# PX4FMUv2_4_6_08.net
KiCad netlist of a schematic drawn in Altium Designer
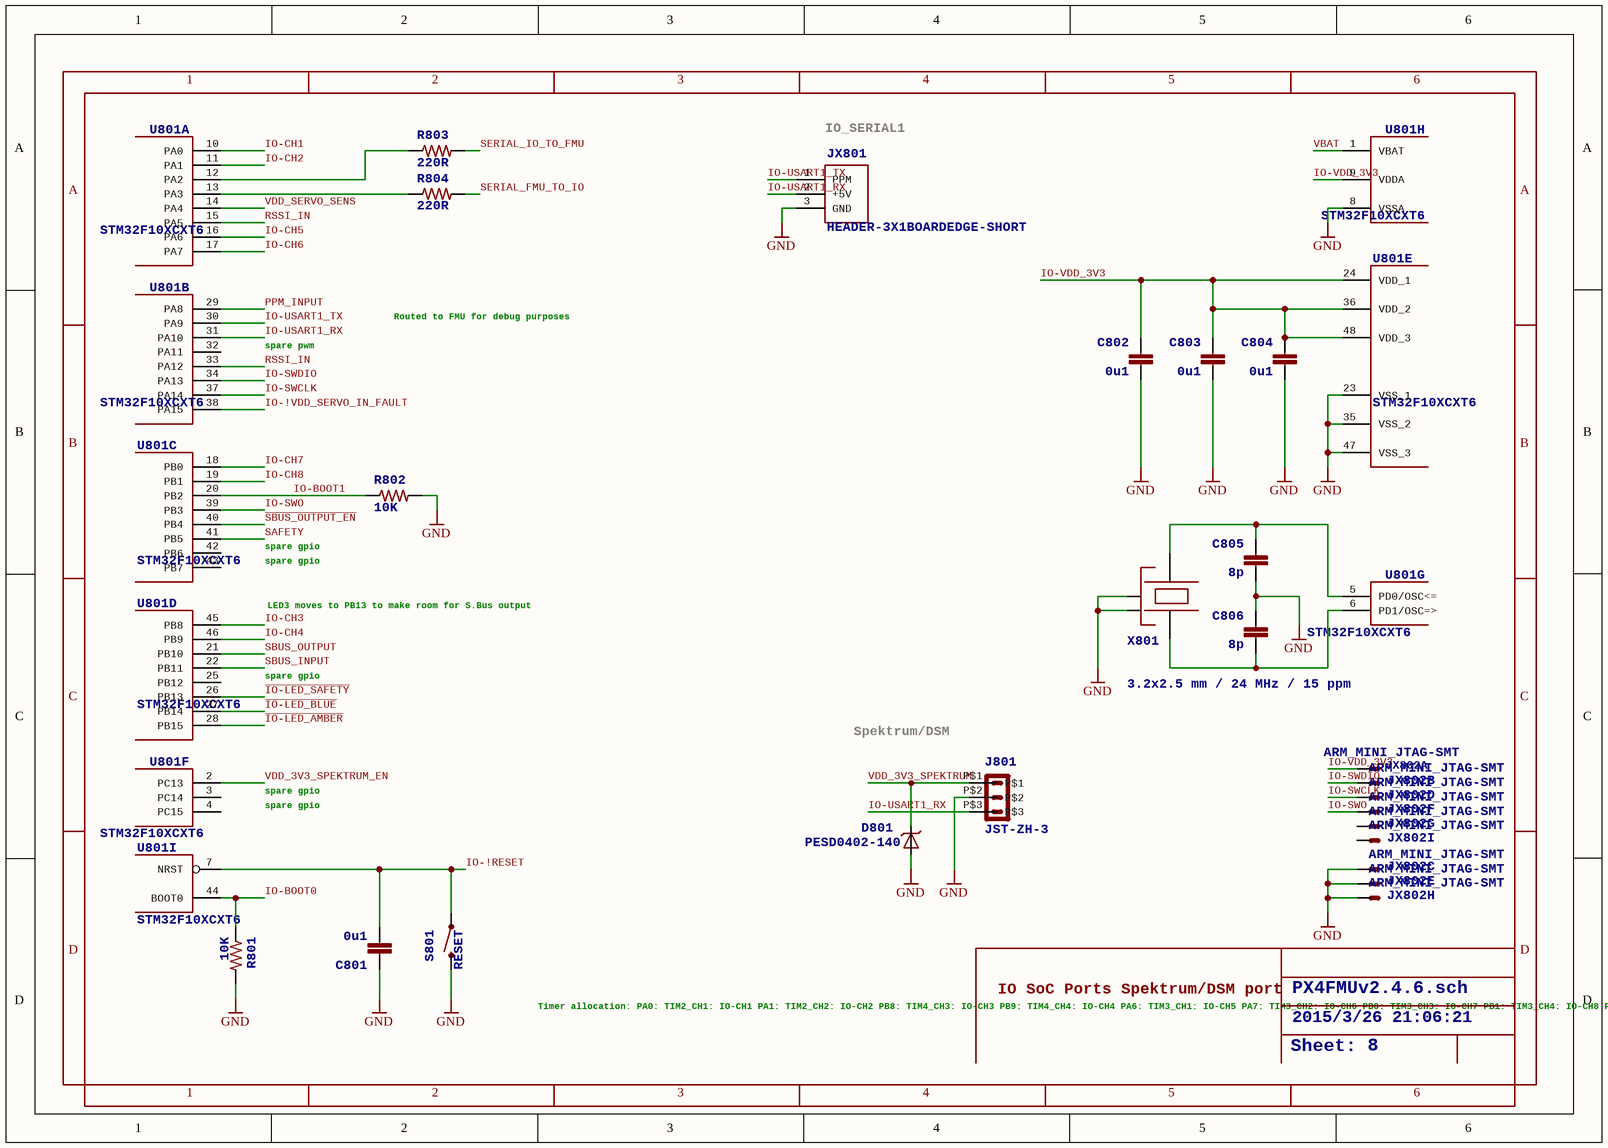
[diagram p0: PX4FMUv2.4.6_08.SchDoc]

(export (version "E")
  (design (tool "Eeschema 10.0.6"))
  (components
    (comp (ref "C801")
      (value "0u1")
      (footprint "0402-CAP")
      (description "<b>Capacitor</b>\nStandard 0603 ceramic capacitor, and 0.1\" leaded capacitor.")
      (fields (field (name "PARTNO") "CC0402ZRY5V7BB104"))
      (libsource (lib "") (part "CAP0402_1"))
    )
    (comp (ref "C802")
      (value "0u1")
      (footprint "0402-CAP")
      (description "<b>Capacitor</b>\nStandard 0603 ceramic capacitor, and 0.1\" leaded capacitor.")
      (fields (field (name "PARTNO") "CC0402ZRY5V7BB104"))
      (libsource (lib "pixhawk2") (part "CAP0402"))
    )
    (comp (ref "C803")
      (value "0u1")
      (footprint "0402-CAP")
      (description "<b>Capacitor</b>\nStandard 0603 ceramic capacitor, and 0.1\" leaded capacitor.")
      (fields (field (name "PARTNO") "CC0402ZRY5V7BB104"))
      (libsource (lib "pixhawk2") (part "CAP0402"))
    )
    (comp (ref "C804")
      (value "0u1")
      (footprint "0402-CAP")
      (description "<b>Capacitor</b>\nStandard 0603 ceramic capacitor, and 0.1\" leaded capacitor.")
      (fields (field (name "PARTNO") "CC0402ZRY5V7BB104"))
      (libsource (lib "pixhawk2") (part "CAP0402"))
    )
    (comp (ref "C805")
      (value "8p")
      (footprint "0402-CAP")
      (description "<b>Capacitor</b>\nStandard 0603 ceramic capacitor, and 0.1\" leaded capacitor.")
      (fields (field (name "PARTNO") "C1005C0G1H080C"))
      (libsource (lib "pixhawk2") (part "CAP0402"))
    )
    (comp (ref "C806")
      (value "8p")
      (footprint "0402-CAP")
      (description "<b>Capacitor</b>\nStandard 0603 ceramic capacitor, and 0.1\" leaded capacitor.")
      (fields (field (name "PARTNO") "C1005C0G1H080C"))
      (libsource (lib "pixhawk2") (part "CAP0402"))
    )
    (comp (ref "D801")
      (value "PESD0402-140")
      (footprint "0402-TVS")
      (libsource (lib "pixhawk2") (part "DIODE-TVS"))
    )
    (comp (ref "J801")
      (value "JST-ZH-3")
      (footprint "JST-ZH-SMT-VERTICAL")
      (fields (field (name "PARTNO") "B3B-ZR-SM4-TF (LF)(SN)(P)"))
      (libsource (lib "for-transfers") (part "JST-ZH-3"))
    )
    (comp (ref "JX801")
      (value "HEADER-3X1BOARDEDGE-SHORT")
      (footprint "HEADER_3X01_SMD_H_BOARD_EDGE_SHORT")
      (description "<h3>Single row 0.1\" servo header</h3>")
      (libsource (lib "pixhawk2") (part "HEADER-3X1BOARDEDGE-SHORT"))
    )
    (comp (ref "JX802")
      (value "ARM_MINI_JTAG-SMT")
      (footprint "FTSH-105-01-XXX-DV-K")
      (description "<b>CONNECTOR</b><p>\nwire to board 1.25 mm (.049 inch) pitch header")
      (fields (field (name "PARTNO") "M50-3900542"))
      (libsource (lib "pixhawk2") (part "ARM_MINI_JTAG-SMT"))
    )
    (comp (ref "R801")
      (value "10K")
      (footprint "0402-RES")
      (fields (field (name "PARTNO") "RC0402FR-0710KL"))
      (libsource (lib "pixhawk2") (part "RESISTOR0402-RES"))
    )
    (comp (ref "R802")
      (value "10K")
      (footprint "0402-RES")
      (fields (field (name "PARTNO") "RC0402FR-0710KL"))
      (libsource (lib "pixhawk2") (part "RESISTOR0402-RES"))
    )
    (comp (ref "R803")
      (value "220R")
      (footprint "0402-RES")
      (fields (field (name "PARTNO") "RC0402FR-07220RL"))
      (libsource (lib "pixhawk2") (part "RESISTOR0402-RES"))
    )
    (comp (ref "R804")
      (value "220R")
      (footprint "0402-RES")
      (fields (field (name "PARTNO") "RC0402FR-07220RL"))
      (libsource (lib "pixhawk2") (part "RESISTOR0402-RES"))
    )
    (comp (ref "S801")
      (value "RESET")
      (footprint "EVQP7J01K")
      (fields (field (name "PARTNO") "EVQ-P7J01P"))
      (libsource (lib "pixhawk2") (part "SWITCH-MOMENTARY-2"))
    )
    (comp (ref "U801")
      (value "STM32F10XCXT6")
      (footprint "TQFP48")
      (description "ST STM32F101/103 48pin LQFP")
      (fields (field (name "PARTNO") "STM32F100C8T6B"))
      (libsource (lib "pixhawk2") (part "STM32F10XCXT6"))
    )
    (comp (ref "X801")
      (value "3.2x2.5 mm / 24 MHz / 15 ppm")
      (footprint "OSCILLATOR-3.2X2.5")
      (description "Crystal Oscillator in 3.2x2.5 SMD")
      (libsource (lib "pixhawk2") (part "OSCILLATOR-3.2X2.5"))
    )
  )
  (nets
    (net (code "1") (name "/IO-!RESET") (class "Default")
      (node (ref "C801") (pin "P$2") (pinfunction "2_P$2") (pintype "passive"))
      (node (ref "S801") (pin "A1") (pinfunction "1_A1") (pintype "passive"))
      (node (ref "U801") (pin "7") (pinfunction "NRST_7") (pintype "passive"))
    )
    (net (code "2") (name "/IO-!VDD_SERVO_IN_FAULT") (class "Default")
      (node (ref "U801") (pin "38") (pinfunction "PA15_38") (pintype "passive"))
    )
    (net (code "3") (name "/IO-BOOT0") (class "Default")
      (node (ref "R801") (pin "P$1") (pinfunction "1_P$1") (pintype "passive"))
      (node (ref "U801") (pin "44") (pinfunction "BOOT0_44") (pintype "passive"))
    )
    (net (code "4") (name "/IO-BOOT1") (class "Default")
      (node (ref "R802") (pin "P$1") (pinfunction "1_P$1") (pintype "passive"))
      (node (ref "U801") (pin "20") (pinfunction "PB2_20") (pintype "passive"))
    )
    (net (code "5") (name "/IO-CH1") (class "Default")
      (node (ref "U801") (pin "10") (pinfunction "PA0_10") (pintype "passive"))
    )
    (net (code "6") (name "/IO-CH2") (class "Default")
      (node (ref "U801") (pin "11") (pinfunction "PA1_11") (pintype "passive"))
    )
    (net (code "7") (name "/IO-CH3") (class "Default")
      (node (ref "U801") (pin "45") (pinfunction "PB8_45") (pintype "passive"))
    )
    (net (code "8") (name "/IO-CH4") (class "Default")
      (node (ref "U801") (pin "46") (pinfunction "PB9_46") (pintype "passive"))
    )
    (net (code "9") (name "/IO-CH5") (class "Default")
      (node (ref "U801") (pin "16") (pinfunction "PA6_16") (pintype "passive"))
    )
    (net (code "10") (name "/IO-CH6") (class "Default")
      (node (ref "U801") (pin "17") (pinfunction "PA7_17") (pintype "passive"))
    )
    (net (code "11") (name "/IO-CH7") (class "Default")
      (node (ref "U801") (pin "18") (pinfunction "PB0_18") (pintype "passive"))
    )
    (net (code "12") (name "/IO-CH8") (class "Default")
      (node (ref "U801") (pin "19") (pinfunction "PB1_19") (pintype "passive"))
    )
    (net (code "13") (name "/IO-SWCLK") (class "Default")
      (node (ref "JX802") (pin "4") (pinfunction "S_4") (pintype "passive"))
      (node (ref "U801") (pin "37") (pinfunction "PA14_37") (pintype "passive"))
    )
    (net (code "14") (name "/IO-SWDIO") (class "Default")
      (node (ref "JX802") (pin "2") (pinfunction "S_2") (pintype "passive"))
      (node (ref "U801") (pin "34") (pinfunction "PA13_34") (pintype "passive"))
    )
    (net (code "15") (name "/IO-SWO") (class "Default")
      (node (ref "JX802") (pin "6") (pinfunction "S_6") (pintype "passive"))
      (node (ref "U801") (pin "39") (pinfunction "PB3_39") (pintype "passive"))
    )
    (net (code "16") (name "/IO-USART1_RX") (class "Default")
      (node (ref "J801") (pin "P$3") (pinfunction "P$3_P$3") (pintype "passive"))
      (node (ref "JX801") (pin "2") (pinfunction "+5V_2") (pintype "passive"))
      (node (ref "U801") (pin "31") (pinfunction "PA10_31") (pintype "passive"))
    )
    (net (code "17") (name "/IO-USART1_TX") (class "Default")
      (node (ref "JX801") (pin "1") (pinfunction "PPM_1") (pintype "passive"))
      (node (ref "U801") (pin "30") (pinfunction "PA9_30") (pintype "passive"))
    )
    (net (code "18") (name "/IO-VDD_3V3") (class "Default")
      (node (ref "C802") (pin "P$1") (pinfunction "1_P$1") (pintype "passive"))
      (node (ref "C803") (pin "P$1") (pinfunction "1_P$1") (pintype "passive"))
      (node (ref "C804") (pin "P$1") (pinfunction "1_P$1") (pintype "passive"))
      (node (ref "JX802") (pin "1") (pinfunction "S_1") (pintype "passive"))
      (node (ref "U801") (pin "24") (pinfunction "VDD_1_24") (pintype "power_in"))
      (node (ref "U801") (pin "36") (pinfunction "VDD_2_36") (pintype "power_in"))
      (node (ref "U801") (pin "48") (pinfunction "VDD_3_48") (pintype "power_in"))
      (node (ref "U801") (pin "9") (pinfunction "VDDA_9") (pintype "power_in"))
    )
    (net (code "19") (name "/PPM_INPUT") (class "Default")
      (node (ref "U801") (pin "29") (pinfunction "PA8_29") (pintype "passive"))
    )
    (net (code "20") (name "/RSSI_IN") (class "Default")
      (node (ref "U801") (pin "15") (pinfunction "PA5_15") (pintype "passive"))
      (node (ref "U801") (pin "33") (pinfunction "PA12_33") (pintype "passive"))
    )
    (net (code "21") (name "/SAFETY") (class "Default")
      (node (ref "U801") (pin "41") (pinfunction "PB5_41") (pintype "passive"))
    )
    (net (code "22") (name "/SBUS_INPUT") (class "Default")
      (node (ref "U801") (pin "22") (pinfunction "PB11_22") (pintype "passive"))
    )
    (net (code "23") (name "/SBUS_OUTPUT") (class "Default")
      (node (ref "U801") (pin "21") (pinfunction "PB10_21") (pintype "passive"))
    )
    (net (code "24") (name "/SERIAL_FMU_TO_IO") (class "Default")
      (node (ref "R804") (pin "P$2") (pinfunction "2_P$2") (pintype "passive"))
    )
    (net (code "25") (name "/SERIAL_IO_TO_FMU") (class "Default")
      (node (ref "R803") (pin "P$2") (pinfunction "2_P$2") (pintype "passive"))
    )
    (net (code "26") (name "/VBAT") (class "Default")
      (node (ref "U801") (pin "1") (pinfunction "VBAT_1") (pintype "power_in"))
    )
    (net (code "27") (name "/VDD_3V3_SPEKTRUM") (class "Default")
      (node (ref "D801") (pin "C") (pinfunction "C_C") (pintype "passive"))
      (node (ref "J801") (pin "P$1") (pinfunction "P$1_P$1") (pintype "passive"))
    )
    (net (code "28") (name "/VDD_3V3_SPEKTRUM_EN") (class "Default")
      (node (ref "U801") (pin "2") (pinfunction "PC13_2") (pintype "passive"))
    )
    (net (code "29") (name "/VDD_SERVO_SENS") (class "Default")
      (node (ref "U801") (pin "14") (pinfunction "PA4_14") (pintype "passive"))
    )
    (net (code "30") (name "/~{IO-LED_AMBER}") (class "Default")
      (node (ref "U801") (pin "28") (pinfunction "PB15_28") (pintype "passive"))
    )
    (net (code "31") (name "/~{IO-LED_BLUE}") (class "Default")
      (node (ref "U801") (pin "27") (pinfunction "PB14_27") (pintype "passive"))
    )
    (net (code "32") (name "/~{IO-LED_SAFETY}") (class "Default")
      (node (ref "U801") (pin "26") (pinfunction "PB13_26") (pintype "passive"))
    )
    (net (code "33") (name "/~{SBUS_OUTPUT_EN}") (class "Default")
      (node (ref "U801") (pin "40") (pinfunction "PB4_40") (pintype "passive"))
    )
    (net (code "34") (name "GND") (class "Default")
      (node (ref "C801") (pin "P$1") (pinfunction "1_P$1") (pintype "passive"))
      (node (ref "C802") (pin "P$2") (pinfunction "2_P$2") (pintype "passive"))
      (node (ref "C803") (pin "P$2") (pinfunction "2_P$2") (pintype "passive"))
      (node (ref "C804") (pin "P$2") (pinfunction "2_P$2") (pintype "passive"))
      (node (ref "C805") (pin "P$2") (pinfunction "2_P$2") (pintype "passive"))
      (node (ref "C806") (pin "P$1") (pinfunction "1_P$1") (pintype "passive"))
      (node (ref "D801") (pin "A") (pinfunction "A_A") (pintype "passive"))
      (node (ref "J801") (pin "P$2") (pinfunction "P$2_P$2") (pintype "passive"))
      (node (ref "JX801") (pin "3") (pinfunction "GND_3") (pintype "passive"))
      (node (ref "JX802") (pin "3") (pinfunction "S_3") (pintype "passive"))
      (node (ref "JX802") (pin "5") (pinfunction "S_5") (pintype "passive"))
      (node (ref "JX802") (pin "9") (pinfunction "S_9") (pintype "passive"))
      (node (ref "R801") (pin "P$2") (pinfunction "2_P$2") (pintype "passive"))
      (node (ref "R802") (pin "P$2") (pinfunction "2_P$2") (pintype "passive"))
      (node (ref "S801") (pin "B3") (pinfunction "2_B3") (pintype "passive"))
      (node (ref "U801") (pin "23") (pinfunction "VSS_1_23") (pintype "power_in"))
      (node (ref "U801") (pin "35") (pinfunction "VSS_2_35") (pintype "power_in"))
      (node (ref "U801") (pin "47") (pinfunction "VSS_3_47") (pintype "power_in"))
      (node (ref "U801") (pin "8") (pinfunction "VSSA_8") (pintype "power_in"))
      (node (ref "X801") (pin "2") (pinfunction "NC_2_2") (pintype "open_emitter"))
      (node (ref "X801") (pin "4") (pinfunction "NC_4_4") (pintype "open_emitter"))
    )
    (net (code "35") (name "Net-(C805-1)") (class "Default")
      (node (ref "C805") (pin "P$1") (pinfunction "1_P$1") (pintype "passive"))
      (node (ref "U801") (pin "5") (pinfunction "PD0/OSC<=_5") (pintype "passive"))
      (node (ref "X801") (pin "3") (pinfunction "3_3") (pintype "passive"))
    )
    (net (code "36") (name "Net-(C806-2)") (class "Default")
      (node (ref "C806") (pin "P$2") (pinfunction "2_P$2") (pintype "passive"))
      (node (ref "U801") (pin "6") (pinfunction "PD1/OSC=>_6") (pintype "passive"))
      (node (ref "X801") (pin "1") (pinfunction "1_1") (pintype "passive"))
    )
    (net (code "37") (name "Net-(R803-1)") (class "Default")
      (node (ref "R803") (pin "P$1") (pinfunction "1_P$1") (pintype "passive"))
      (node (ref "U801") (pin "12") (pinfunction "PA2_12") (pintype "passive"))
    )
    (net (code "38") (name "Net-(R804-1)") (class "Default")
      (node (ref "R804") (pin "P$1") (pinfunction "1_P$1") (pintype "passive"))
      (node (ref "U801") (pin "13") (pinfunction "PA3_13") (pintype "passive"))
    )
    (net (code "39") (name "unconnected-(JX802G-S-Pad8)") (class "Default")
      (node (ref "JX802") (pin "8") (pinfunction "S_8") (pintype "passive"))
    )
    (net (code "40") (name "unconnected-(JX802I-S-Pad10)") (class "Default")
      (node (ref "JX802") (pin "10") (pinfunction "S_10") (pintype "passive"))
    )
    (net (code "41") (name "unconnected-(U801B-PA11-Pad32)") (class "Default")
      (node (ref "U801") (pin "32") (pinfunction "PA11_32") (pintype "passive"))
    )
    (net (code "42") (name "unconnected-(U801C-PB6-Pad42)") (class "Default")
      (node (ref "U801") (pin "42") (pinfunction "PB6_42") (pintype "passive"))
    )
    (net (code "43") (name "unconnected-(U801C-PB7-Pad43)") (class "Default")
      (node (ref "U801") (pin "43") (pinfunction "PB7_43") (pintype "passive"))
    )
    (net (code "44") (name "unconnected-(U801D-PB12-Pad25)") (class "Default")
      (node (ref "U801") (pin "25") (pinfunction "PB12_25") (pintype "passive"))
    )
    (net (code "45") (name "unconnected-(U801F-PC14-Pad3)") (class "Default")
      (node (ref "U801") (pin "3") (pinfunction "PC14_3") (pintype "passive"))
    )
    (net (code "46") (name "unconnected-(U801F-PC15-Pad4)") (class "Default")
      (node (ref "U801") (pin "4") (pinfunction "PC15_4") (pintype "passive"))
    )
  )
)
